# EbowPlaca.net
KiCad netlist of a schematic drawn in EAGLE
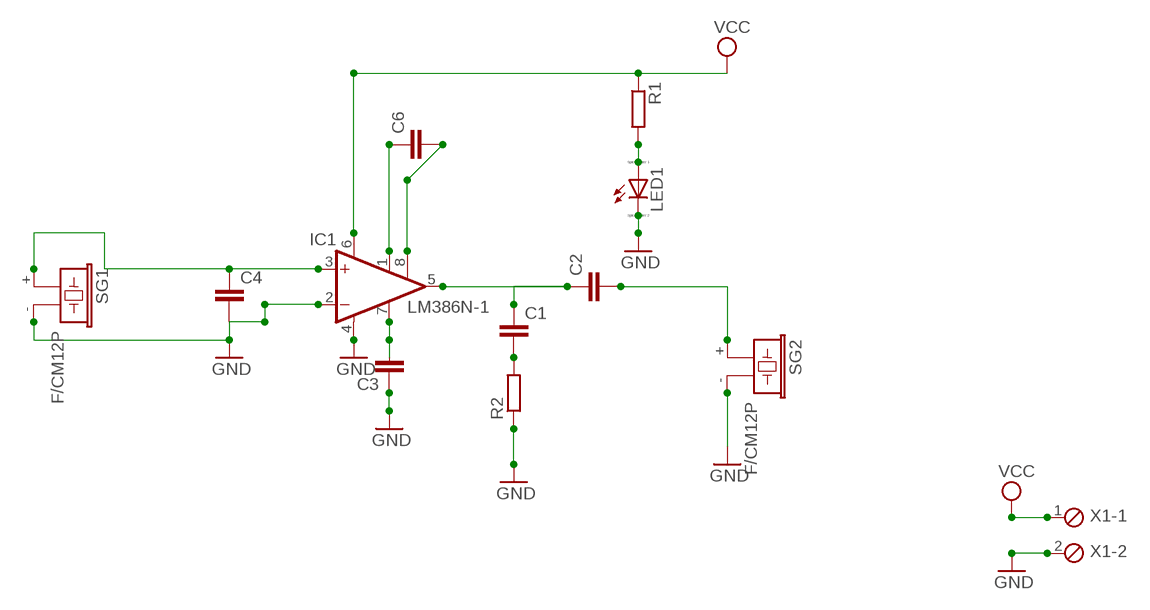
[diagram p0: schematic, sheet 1]

(export (version "E")
  (design (tool "Eeschema 10.0.6"))
  (components
    (comp (ref "C1")
      (value "C5/3")
      (footprint "eagle-import:C5B3")
      (libsource (lib "eagle-import") (part "C5/3"))
    )
    (comp (ref "C2")
      (value "C5/2.5")
      (footprint "eagle-import:C5B2.5")
      (libsource (lib "eagle-import") (part "C5/2.5"))
    )
    (comp (ref "C3")
      (value "C2.5/5")
      (footprint "eagle-import:C2.5-5")
      (libsource (lib "eagle-import") (part "C2.5/5"))
    )
    (comp (ref "C4")
      (value "C2.5/4")
      (footprint "eagle-import:C2.5-4")
      (libsource (lib "eagle-import") (part "C2.5/4"))
    )
    (comp (ref "C6")
      (value "C5/3")
      (footprint "eagle-import:C5B3")
      (libsource (lib "eagle-import") (part "C5/3"))
    )
    (comp (ref "IC1")
      (value "LM386N-1")
      (footprint "eagle-import:DIL08")
      (libsource (lib "eagle-import") (part "LM386?-N1"))
    )
    (comp (ref "LED1")
      (value "LED_ELD260")
      (footprint "eagle-import:LED_LD260")
      (libsource (lib "eagle-import") (part "LED_ELD260"))
    )
    (comp (ref "R1")
      (value "R-EU_0207/10")
      (footprint "eagle-import:0207_10")
      (libsource (lib "eagle-import") (part "R-EU_0207/10"))
    )
    (comp (ref "R2")
      (value "R-EU_0207/10")
      (footprint "eagle-import:0207_10")
      (libsource (lib "eagle-import") (part "R-EU_0207/10"))
    )
    (comp (ref "SG1")
      (value "F/CM12P")
      (footprint "eagle-import:F_CM12P")
      (libsource (lib "eagle-import") (part "F/CM12P"))
    )
    (comp (ref "SG2")
      (value "F/CM12P")
      (footprint "eagle-import:F_CM12P")
      (libsource (lib "eagle-import") (part "F/CM12P"))
    )
    (comp (ref "X1")
      (value "MPT2")
      (footprint "eagle-import:2POL254")
      (libsource (lib "eagle-import") (part "MPT2"))
    )
  )
  (nets
    (net (code "1") (name "GND") (class "Default")
      (node (ref "C3") (pin "1") (pinfunction "1_1") (pintype "passive"))
      (node (ref "C4") (pin "2") (pinfunction "2_2") (pintype "passive"))
      (node (ref "IC1") (pin "2") (pinfunction "-IN_2") (pintype "input"))
      (node (ref "IC1") (pin "4") (pinfunction "GND_4") (pintype "power_in"))
      (node (ref "LED1") (pin "K") (pinfunction "C_K") (pintype "passive"))
      (node (ref "R2") (pin "1") (pinfunction "1_1") (pintype "passive"))
      (node (ref "SG1") (pin "-") (pinfunction "2_-") (pintype "passive"))
      (node (ref "SG2") (pin "-") (pinfunction "2_-") (pintype "passive"))
      (node (ref "X1") (pin "2") (pinfunction "1_2") (pintype "passive"))
    )
    (net (code "2") (name "Net-(C1-Pad2)") (class "Default")
      (node (ref "C1") (pin "2") (pinfunction "2_2") (pintype "passive"))
      (node (ref "R2") (pin "2") (pinfunction "2_2") (pintype "passive"))
    )
    (net (code "3") (name "Net-(C6-Pad1)") (class "Default")
      (node (ref "C6") (pin "1") (pinfunction "1_1") (pintype "passive"))
      (node (ref "IC1") (pin "1") (pinfunction "GAIN_1") (pintype "passive"))
    )
    (net (code "4") (name "Net-(C6-Pad2)") (class "Default")
      (node (ref "C6") (pin "2") (pinfunction "2_2") (pintype "passive"))
      (node (ref "IC1") (pin "8") (pinfunction "GAIN_8") (pintype "passive"))
    )
    (net (code "5") (name "Net-(IC1-+IN)") (class "Default")
      (node (ref "C4") (pin "1") (pinfunction "1_1") (pintype "passive"))
      (node (ref "IC1") (pin "3") (pinfunction "+IN_3") (pintype "input"))
      (node (ref "SG1") (pin "+") (pinfunction "1_+") (pintype "passive"))
    )
    (net (code "6") (name "Net-(IC1-BYPASS)") (class "Default")
      (node (ref "C3") (pin "2") (pinfunction "2_2") (pintype "passive"))
      (node (ref "IC1") (pin "7") (pinfunction "BYPASS_7") (pintype "passive"))
    )
    (net (code "7") (name "Net-(IC1-OUT)") (class "Default")
      (node (ref "C1") (pin "1") (pinfunction "1_1") (pintype "passive"))
      (node (ref "C2") (pin "1") (pinfunction "1_1") (pintype "passive"))
      (node (ref "IC1") (pin "5") (pinfunction "OUT_5") (pintype "output"))
    )
    (net (code "8") (name "Net-(LED1-PadA)") (class "Default")
      (node (ref "LED1") (pin "A") (pinfunction "A_A") (pintype "passive"))
      (node (ref "R1") (pin "2") (pinfunction "2_2") (pintype "passive"))
    )
    (net (code "9") (name "Net-(SG2-1)") (class "Default")
      (node (ref "C2") (pin "2") (pinfunction "2_2") (pintype "passive"))
      (node (ref "SG2") (pin "+") (pinfunction "1_+") (pintype "passive"))
    )
    (net (code "10") (name "VCC") (class "Default")
      (node (ref "IC1") (pin "6") (pinfunction "VS_6") (pintype "power_in"))
      (node (ref "R1") (pin "1") (pinfunction "1_1") (pintype "passive"))
      (node (ref "X1") (pin "1") (pinfunction "1_1") (pintype "passive"))
    )
  )
)
